# mobile-lipo-charger-v0001.net
KiCad netlist of a schematic drawn in EAGLE
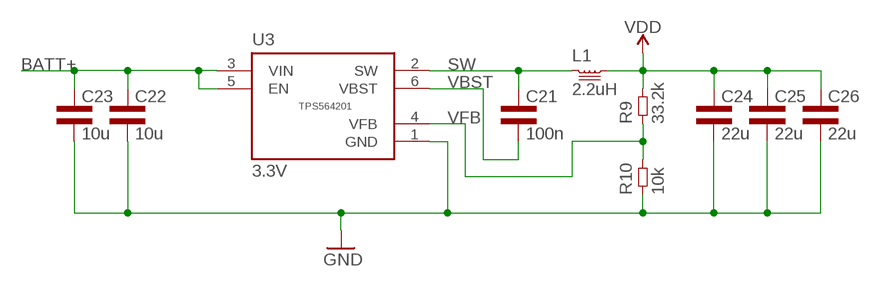
[diagram p0: schematic, sheet 1]
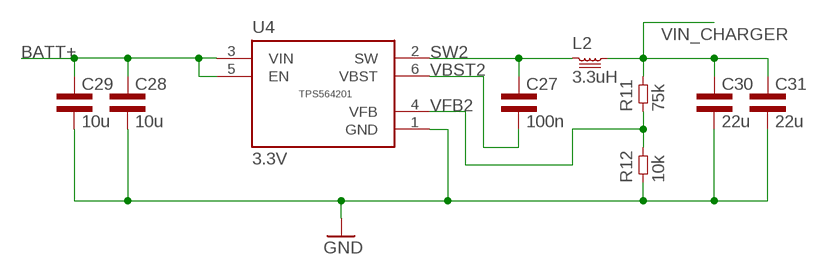
[diagram p1: schematic, sheet 2]
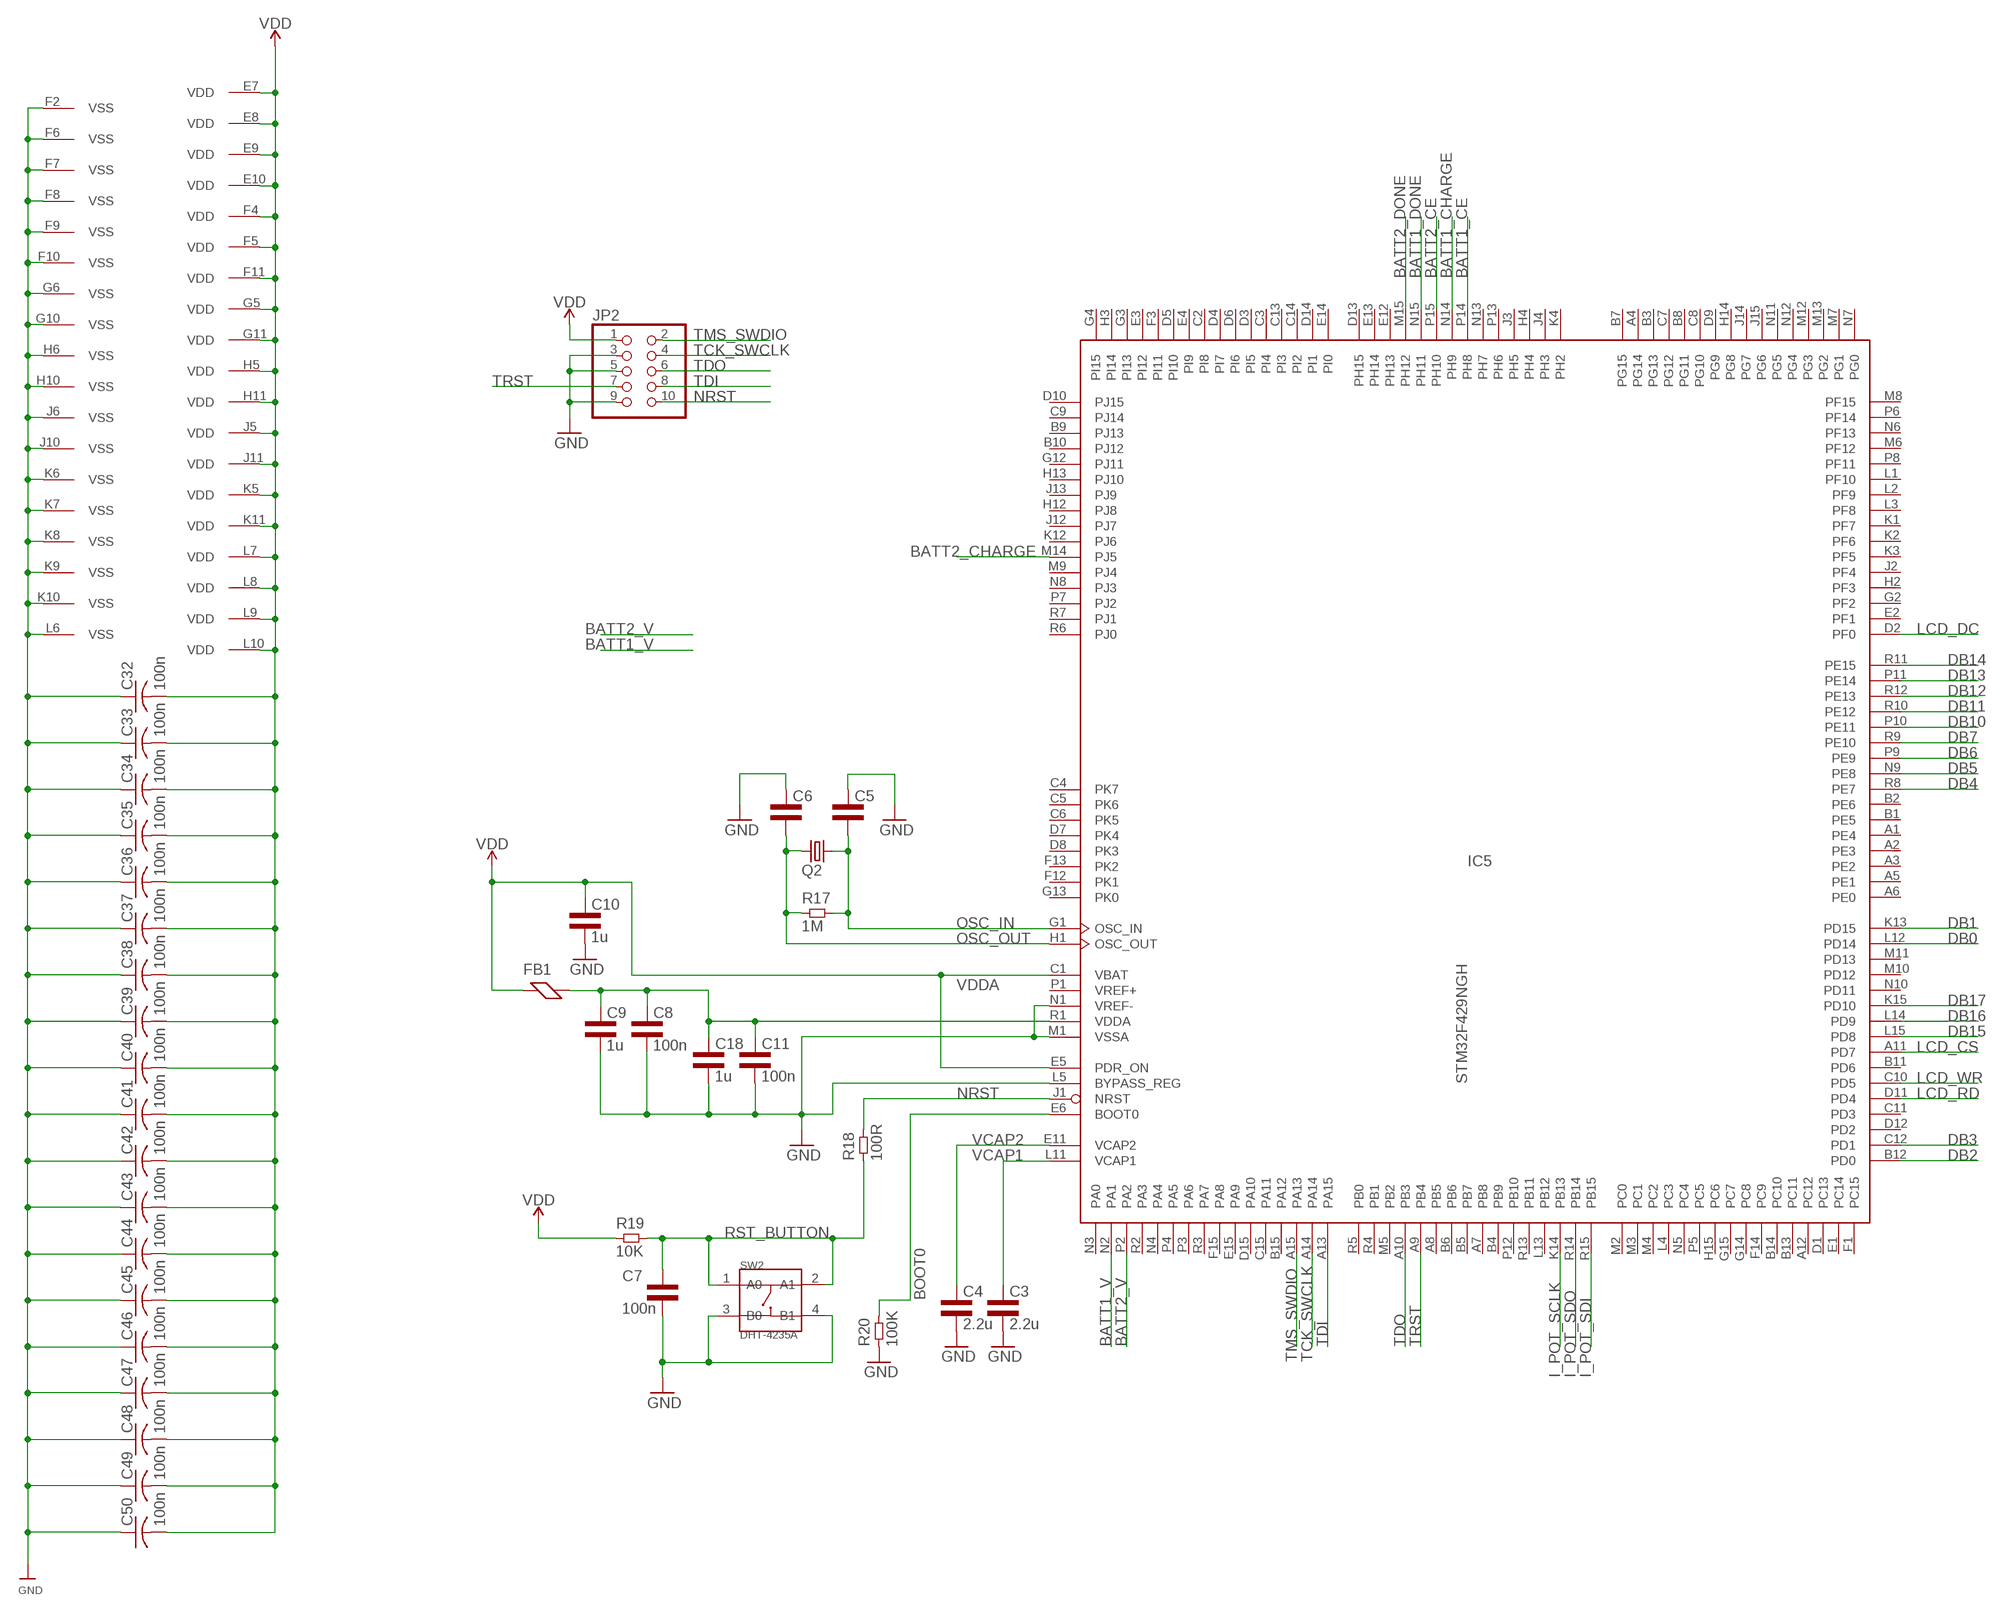
[diagram p2: schematic, sheet 3]
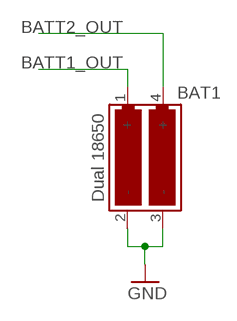
[diagram p3: schematic, sheet 4]
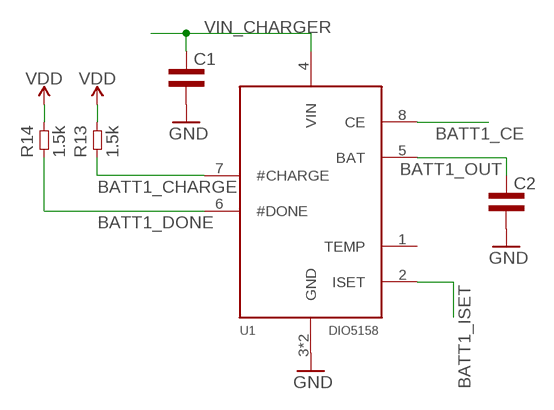
[diagram p4: schematic, sheet 5]
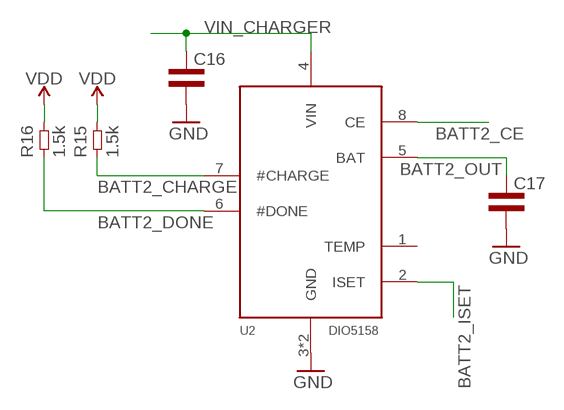
[diagram p5: schematic, sheet 6]
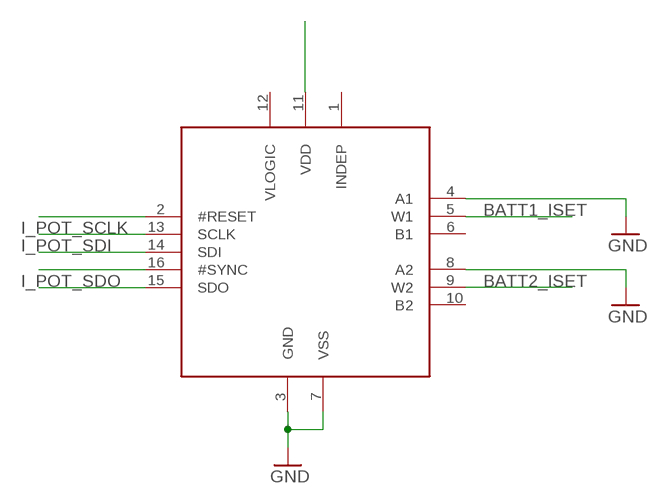
[diagram p6: schematic, sheet 7]
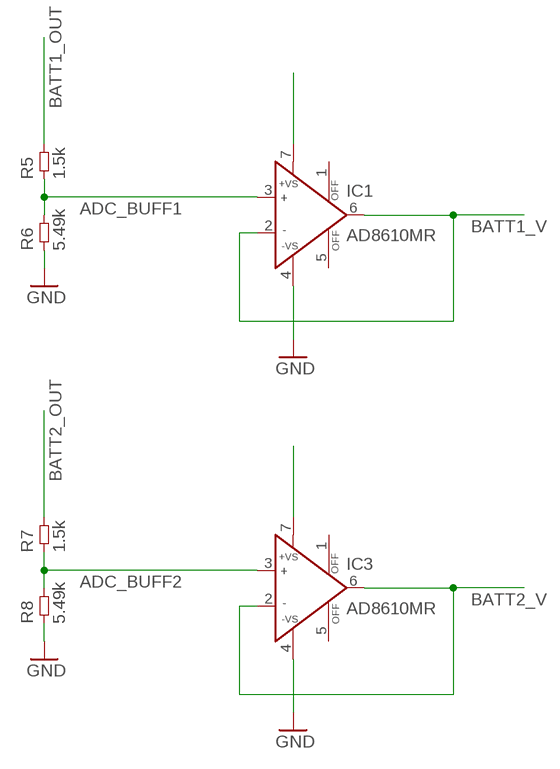
[diagram p7: schematic, sheet 8]
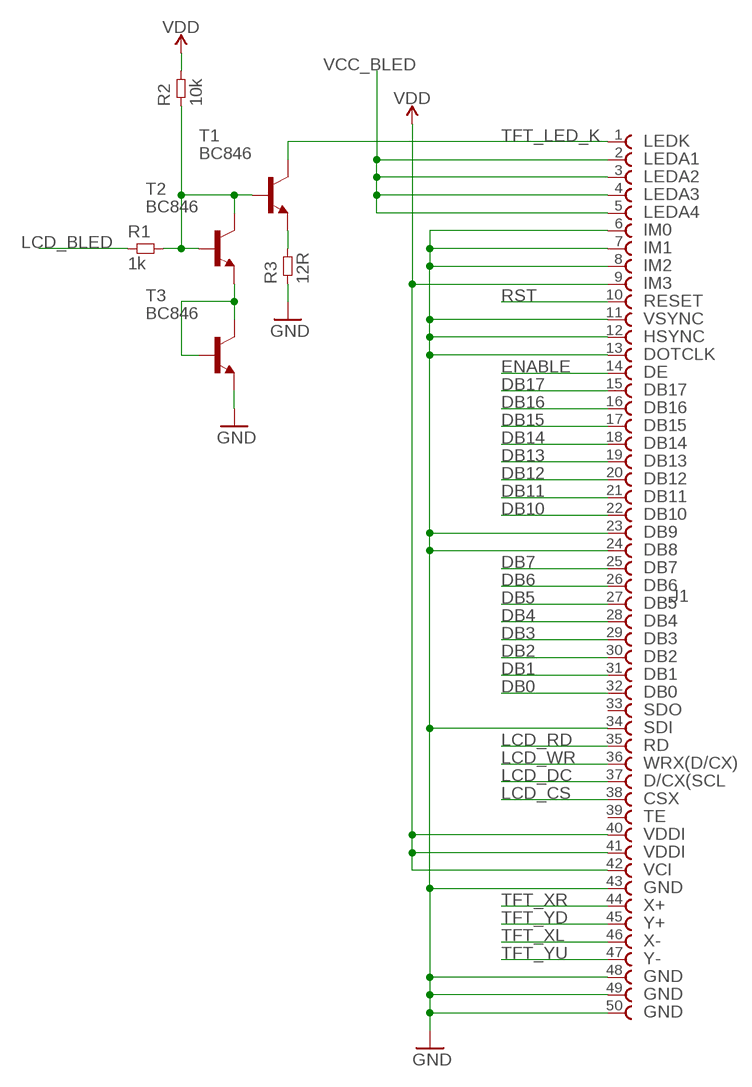
[diagram p8: schematic, sheet 9]

(export (version "E")
  (design (tool "Eeschema 10.0.6"))
  (components
    (comp (ref "C16")
      (value "CAP0805L3")
      (footprint "eagle-import:0805L3")
      (libsource (lib "eagle-import") (part "CAP0805L3"))
    )
    (comp (ref "C17")
      (value "CAP0805L3")
      (footprint "eagle-import:0805L3")
      (libsource (lib "eagle-import") (part "CAP0805L3"))
    )
    (comp (ref "R15")
      (value "1.5k")
      (footprint "eagle-import:0603L3")
      (libsource (lib "eagle-import") (part "RES0603L3"))
    )
    (comp (ref "R16")
      (value "1.5k")
      (footprint "eagle-import:0603L3")
      (libsource (lib "eagle-import") (part "RES0603L3"))
    )
    (comp (ref "U2")
      (value "DIO5158XS8")
      (footprint "eagle-import:EP-MSOP8")
      (libsource (lib "eagle-import") (part "DIO5158XS8"))
    )
    (comp (ref "C3")
      (value "2.2u")
      (footprint "eagle-import:0805L3")
      (fields (field (name "MANUFACTURER") "AVX"))
      (libsource (lib "eagle-import") (part "CAP0805L3"))
    )
    (comp (ref "C4")
      (value "2.2u")
      (footprint "eagle-import:0805L3")
      (fields (field (name "MANUFACTURER") "AVX"))
      (libsource (lib "eagle-import") (part "CAP0805L3"))
    )
    (comp (ref "C5")
      (value "CAP0603L3")
      (footprint "eagle-import:0603L3")
      (libsource (lib "eagle-import") (part "CAP0603L3"))
    )
    (comp (ref "C6")
      (value "CAP0603L3")
      (footprint "eagle-import:0603L3")
      (libsource (lib "eagle-import") (part "CAP0603L3"))
    )
    (comp (ref "C7")
      (value "100n")
      (footprint "eagle-import:0402L3")
      (libsource (lib "eagle-import") (part "CAP0402L3"))
    )
    (comp (ref "C8")
      (value "100n")
      (footprint "eagle-import:0402L3")
      (libsource (lib "eagle-import") (part "CAP0402L3"))
    )
    (comp (ref "C9")
      (value "1u")
      (footprint "eagle-import:0805L3")
      (libsource (lib "eagle-import") (part "CAP0805L3"))
    )
    (comp (ref "C10")
      (value "1u")
      (footprint "eagle-import:0603L3")
      (libsource (lib "eagle-import") (part "CAP0603L3"))
    )
    (comp (ref "C11")
      (value "100n")
      (footprint "eagle-import:0402L3")
      (libsource (lib "eagle-import") (part "CAP0402L3"))
    )
    (comp (ref "C18")
      (value "1u")
      (footprint "eagle-import:0805L3")
      (libsource (lib "eagle-import") (part "CAP0805L3"))
    )
    (comp (ref "C32")
      (value "100n")
      (footprint "eagle-import:C0201")
      (libsource (lib "eagle-import") (part "C-USC0201"))
    )
    (comp (ref "C33")
      (value "100n")
      (footprint "eagle-import:C0201")
      (libsource (lib "eagle-import") (part "C-USC0201"))
    )
    (comp (ref "C34")
      (value "100n")
      (footprint "eagle-import:C0201")
      (libsource (lib "eagle-import") (part "C-USC0201"))
    )
    (comp (ref "C35")
      (value "100n")
      (footprint "eagle-import:C0201")
      (libsource (lib "eagle-import") (part "C-USC0201"))
    )
    (comp (ref "C36")
      (value "100n")
      (footprint "eagle-import:C0201")
      (libsource (lib "eagle-import") (part "C-USC0201"))
    )
    (comp (ref "C37")
      (value "100n")
      (footprint "eagle-import:C0201")
      (libsource (lib "eagle-import") (part "C-USC0201"))
    )
    (comp (ref "C38")
      (value "100n")
      (footprint "eagle-import:C0201")
      (libsource (lib "eagle-import") (part "C-USC0201"))
    )
    (comp (ref "C39")
      (value "100n")
      (footprint "eagle-import:C0201")
      (libsource (lib "eagle-import") (part "C-USC0201"))
    )
    (comp (ref "C40")
      (value "100n")
      (footprint "eagle-import:C0201")
      (libsource (lib "eagle-import") (part "C-USC0201"))
    )
    (comp (ref "C41")
      (value "100n")
      (footprint "eagle-import:C0201")
      (libsource (lib "eagle-import") (part "C-USC0201"))
    )
    (comp (ref "C42")
      (value "100n")
      (footprint "eagle-import:C0201")
      (libsource (lib "eagle-import") (part "C-USC0201"))
    )
    (comp (ref "C43")
      (value "100n")
      (footprint "eagle-import:C0201")
      (libsource (lib "eagle-import") (part "C-USC0201"))
    )
    (comp (ref "C44")
      (value "100n")
      (footprint "eagle-import:C0201")
      (libsource (lib "eagle-import") (part "C-USC0201"))
    )
    (comp (ref "C45")
      (value "100n")
      (footprint "eagle-import:C0201")
      (libsource (lib "eagle-import") (part "C-USC0201"))
    )
    (comp (ref "C46")
      (value "100n")
      (footprint "eagle-import:C0201")
      (libsource (lib "eagle-import") (part "C-USC0201"))
    )
    (comp (ref "C47")
      (value "100n")
      (footprint "eagle-import:C0201")
      (libsource (lib "eagle-import") (part "C-USC0201"))
    )
    (comp (ref "C48")
      (value "100n")
      (footprint "eagle-import:C0201")
      (libsource (lib "eagle-import") (part "C-USC0201"))
    )
    (comp (ref "C49")
      (value "100n")
      (footprint "eagle-import:C0201")
      (libsource (lib "eagle-import") (part "C-USC0201"))
    )
    (comp (ref "C50")
      (value "100n")
      (footprint "eagle-import:C0201")
      (libsource (lib "eagle-import") (part "C-USC0201"))
    )
    (comp (ref "FB1")
      (value "FERRITE0603L3")
      (footprint "eagle-import:0603L3")
      (libsource (lib "eagle-import") (part "FERRITE0603L3"))
    )
    (comp (ref "IC5")
      (value "STM32F429NGH")
      (footprint "eagle-import:TFBGA216")
      (libsource (lib "eagle-import") (part "STM32F429NHG"))
    )
    (comp (ref "JP2")
      (value "PINHD-2X5")
      (footprint "eagle-import:2X05")
      (libsource (lib "eagle-import") (part "PINHD-2X5"))
    )
    (comp (ref "Q2")
      (value "CRYSTALHC49US")
      (footprint "eagle-import:PCM2707_V1_SPARKFUN_HC49US")
      (libsource (lib "eagle-import") (part "CRYSTALHC49US"))
    )
    (comp (ref "R17")
      (value "1M")
      (footprint "eagle-import:0603L3")
      (libsource (lib "eagle-import") (part "RES0603L3"))
    )
    (comp (ref "R18")
      (value "100R")
      (footprint "eagle-import:0603L3")
      (libsource (lib "eagle-import") (part "RES0603L3"))
    )
    (comp (ref "R19")
      (value "10K")
      (footprint "eagle-import:0603L3")
      (libsource (lib "eagle-import") (part "RES0603L3"))
    )
    (comp (ref "R20")
      (value "100K")
      (footprint "eagle-import:0603L3")
      (libsource (lib "eagle-import") (part "RES0603L3"))
    )
    (comp (ref "SW2")
      (value "DHT-4235A")
      (footprint "eagle-import:SW4-SMD-4.2X3.2X2.5MM")
      (libsource (lib "eagle-import") (part "SMD-BUTTON-TOP-DHT-4235A(4P-4.2X3.2MM)"))
    )
    (comp (ref "U$1")
      (value "AD5122BRUZ10")
      (footprint "eagle-import:TSSOP-RU-16")
      (fields (field (name "MANUFACTURER") "Analog Devices"))
      (libsource (lib "eagle-import") (part "AD5122BRUZ10"))
    )
    (comp (ref "C27")
      (value "100n")
      (footprint "eagle-import:0603L3")
      (libsource (lib "eagle-import") (part "CAP0603L3"))
    )
    (comp (ref "C28")
      (value "10u")
      (footprint "eagle-import:1206L3")
      (libsource (lib "eagle-import") (part "CAP1206L3"))
    )
    (comp (ref "C29")
      (value "10u")
      (footprint "eagle-import:1206L3")
      (libsource (lib "eagle-import") (part "CAP1206L3"))
    )
    (comp (ref "C30")
      (value "22u")
      (footprint "eagle-import:0603L3")
      (libsource (lib "eagle-import") (part "CAP0603L3"))
    )
    (comp (ref "C31")
      (value "22u")
      (footprint "eagle-import:0603L3")
      (libsource (lib "eagle-import") (part "CAP0603L3"))
    )
    (comp (ref "L2")
      (value "3.3uH")
      (footprint "eagle-import:6X6")
      (fields (field (name "MANUFACTURER") "TDK"))
      (libsource (lib "eagle-import") (part "INDUCTOR6X6"))
    )
    (comp (ref "R11")
      (value "75k")
      (footprint "eagle-import:0402L3")
      (libsource (lib "eagle-import") (part "RES0402L3"))
    )
    (comp (ref "R12")
      (value "10k")
      (footprint "eagle-import:0402L3")
      (libsource (lib "eagle-import") (part "RES0402L3"))
    )
    (comp (ref "U4")
      (value "3.3V")
      (footprint "eagle-import:SOT-1.1")
      (libsource (lib "eagle-import") (part "TPS564201"))
    )
    (comp (ref "BAT1")
      (value "KEYSTONE1048")
      (footprint "eagle-import:KEYSTONE1048")
      (libsource (lib "eagle-import") (part "KEYSTONE1048"))
    )
    (comp (ref "C1")
      (value "CAP0805L3")
      (footprint "eagle-import:0805L3")
      (libsource (lib "eagle-import") (part "CAP0805L3"))
    )
    (comp (ref "C2")
      (value "CAP0805L3")
      (footprint "eagle-import:0805L3")
      (libsource (lib "eagle-import") (part "CAP0805L3"))
    )
    (comp (ref "R13")
      (value "1.5k")
      (footprint "eagle-import:0603L3")
      (libsource (lib "eagle-import") (part "RES0603L3"))
    )
    (comp (ref "R14")
      (value "1.5k")
      (footprint "eagle-import:0603L3")
      (libsource (lib "eagle-import") (part "RES0603L3"))
    )
    (comp (ref "U1")
      (value "DIO5158XS8")
      (footprint "eagle-import:EP-MSOP8")
      (libsource (lib "eagle-import") (part "DIO5158XS8"))
    )
    (comp (ref "J1")
      (value "68715014022")
      (footprint "eagle-import:68715014022")
      (libsource (lib "eagle-import") (part "68715014022"))
    )
    (comp (ref "R1")
      (value "1k")
      (footprint "eagle-import:0603L3")
      (libsource (lib "eagle-import") (part "RES0603L3"))
    )
    (comp (ref "R2")
      (value "10k")
      (footprint "eagle-import:0603L3")
      (libsource (lib "eagle-import") (part "RES0603L3"))
    )
    (comp (ref "R3")
      (value "12R")
      (footprint "eagle-import:0603L3")
      (libsource (lib "eagle-import") (part "RES0603L3"))
    )
    (comp (ref "T1")
      (value "BC846")
      (footprint "eagle-import:SOT23")
      (libsource (lib "eagle-import") (part "BC846"))
    )
    (comp (ref "T2")
      (value "BC846")
      (footprint "eagle-import:SOT23")
      (libsource (lib "eagle-import") (part "BC846"))
    )
    (comp (ref "T3")
      (value "BC846")
      (footprint "eagle-import:SOT23")
      (libsource (lib "eagle-import") (part "BC846"))
    )
    (comp (ref "IC1")
      (value "AD8610MR")
      (footprint "eagle-import:MSOP08")
      (fields (field (name "MF") "ALTERA CORPORATION") (field (name "MPN") "AD8610ARMZ-REEL"))
      (libsource (lib "eagle-import") (part "AD8610MR"))
    )
    (comp (ref "IC3")
      (value "AD8610MR")
      (footprint "eagle-import:MSOP08")
      (fields (field (name "MF") "ALTERA CORPORATION") (field (name "MPN") "AD8610ARMZ-REEL"))
      (libsource (lib "eagle-import") (part "AD8610MR"))
    )
    (comp (ref "R5")
      (value "1.5k")
      (footprint "eagle-import:0603L3")
      (libsource (lib "eagle-import") (part "RES0603L3"))
    )
    (comp (ref "R6")
      (value "5.49k")
      (footprint "eagle-import:0603L3")
      (libsource (lib "eagle-import") (part "RES0603L3"))
    )
    (comp (ref "R7")
      (value "1.5k")
      (footprint "eagle-import:0603L3")
      (libsource (lib "eagle-import") (part "RES0603L3"))
    )
    (comp (ref "R8")
      (value "5.49k")
      (footprint "eagle-import:0603L3")
      (libsource (lib "eagle-import") (part "RES0603L3"))
    )
    (comp (ref "C21")
      (value "100n")
      (footprint "eagle-import:0603L3")
      (libsource (lib "eagle-import") (part "CAP0603L3"))
    )
    (comp (ref "C22")
      (value "10u")
      (footprint "eagle-import:1206L3")
      (libsource (lib "eagle-import") (part "CAP1206L3"))
    )
    (comp (ref "C23")
      (value "10u")
      (footprint "eagle-import:1206L3")
      (libsource (lib "eagle-import") (part "CAP1206L3"))
    )
    (comp (ref "C24")
      (value "22u")
      (footprint "eagle-import:0603L3")
      (libsource (lib "eagle-import") (part "CAP0603L3"))
    )
    (comp (ref "C25")
      (value "22u")
      (footprint "eagle-import:0603L3")
      (libsource (lib "eagle-import") (part "CAP0603L3"))
    )
    (comp (ref "C26")
      (value "22u")
      (footprint "eagle-import:0603L3")
      (libsource (lib "eagle-import") (part "CAP0603L3"))
    )
    (comp (ref "L1")
      (value "2.2uH")
      (footprint "eagle-import:6X6")
      (fields (field (name "MANUFACTURER") "TDK"))
      (libsource (lib "eagle-import") (part "INDUCTOR6X6"))
    )
    (comp (ref "R9")
      (value "33.2k")
      (footprint "eagle-import:0402L3")
      (libsource (lib "eagle-import") (part "RES0402L3"))
    )
    (comp (ref "R10")
      (value "10k")
      (footprint "eagle-import:0402L3")
      (libsource (lib "eagle-import") (part "RES0402L3"))
    )
    (comp (ref "U3")
      (value "3.3V")
      (footprint "eagle-import:SOT-1.1")
      (libsource (lib "eagle-import") (part "TPS564201"))
    )
  )
  (nets
    (net (code "1") (name "ADC_BUFF1") (class "Default")
      (node (ref "IC1") (pin "3") (pinfunction "IN+_3") (pintype "input"))
      (node (ref "R5") (pin "P$1") (pinfunction "1_P$1") (pintype "bidirectional"))
      (node (ref "R6") (pin "P$2") (pinfunction "2_P$2") (pintype "bidirectional"))
    )
    (net (code "2") (name "ADC_BUFF2") (class "Default")
      (node (ref "IC3") (pin "3") (pinfunction "IN+_3") (pintype "input"))
      (node (ref "R7") (pin "P$1") (pinfunction "1_P$1") (pintype "bidirectional"))
      (node (ref "R8") (pin "P$2") (pinfunction "2_P$2") (pintype "bidirectional"))
    )
    (net (code "3") (name "BATT+") (class "Default")
      (node (ref "C22") (pin "1") (pinfunction "1_1") (pintype "bidirectional"))
      (node (ref "C23") (pin "1") (pinfunction "1_1") (pintype "bidirectional"))
      (node (ref "C28") (pin "1") (pinfunction "1_1") (pintype "bidirectional"))
      (node (ref "C29") (pin "1") (pinfunction "1_1") (pintype "bidirectional"))
      (node (ref "U3") (pin "3") (pinfunction "VIN_3") (pintype "bidirectional"))
      (node (ref "U3") (pin "5") (pinfunction "EN_5") (pintype "bidirectional"))
      (node (ref "U4") (pin "3") (pinfunction "VIN_3") (pintype "bidirectional"))
      (node (ref "U4") (pin "5") (pinfunction "EN_5") (pintype "bidirectional"))
    )
    (net (code "4") (name "BATT1_CE") (class "Default")
      (node (ref "IC5") (pin "P14") (pinfunction "PH8_P14") (pintype "bidirectional"))
      (node (ref "U1") (pin "8") (pinfunction "CE_8") (pintype "bidirectional"))
    )
    (net (code "5") (name "BATT1_CHARGE") (class "Default")
      (node (ref "IC5") (pin "N14") (pinfunction "PH9_N14") (pintype "bidirectional"))
      (node (ref "R13") (pin "P$1") (pinfunction "1_P$1") (pintype "bidirectional"))
      (node (ref "U1") (pin "7") (pinfunction "#CHARGE_7") (pintype "bidirectional"))
    )
    (net (code "6") (name "BATT1_DONE") (class "Default")
      (node (ref "IC5") (pin "N15") (pinfunction "PH11_N15") (pintype "bidirectional"))
      (node (ref "R14") (pin "P$1") (pinfunction "1_P$1") (pintype "bidirectional"))
      (node (ref "U1") (pin "6") (pinfunction "#DONE_6") (pintype "bidirectional"))
    )
    (net (code "7") (name "BATT1_ISET") (class "Default")
      (node (ref "U$1") (pin "5") (pinfunction "W1_5") (pintype "bidirectional"))
      (node (ref "U1") (pin "2") (pinfunction "ISET_2") (pintype "bidirectional"))
    )
    (net (code "8") (name "BATT1_OUT") (class "Default")
      (node (ref "BAT1") (pin "1") (pinfunction "+_1") (pintype "bidirectional"))
      (node (ref "C2") (pin "1") (pinfunction "1_1") (pintype "bidirectional"))
      (node (ref "R5") (pin "P$2") (pinfunction "2_P$2") (pintype "bidirectional"))
      (node (ref "U1") (pin "5") (pinfunction "BAT_5") (pintype "bidirectional"))
    )
    (net (code "9") (name "BATT1_V") (class "Default")
      (node (ref "IC1") (pin "2") (pinfunction "IN-_2") (pintype "input"))
      (node (ref "IC1") (pin "6") (pinfunction "OUT_6") (pintype "output"))
      (node (ref "IC5") (pin "N2") (pinfunction "PA1_N2") (pintype "bidirectional"))
    )
    (net (code "10") (name "BATT2_CE") (class "Default")
      (node (ref "IC5") (pin "P15") (pinfunction "PH10_P15") (pintype "bidirectional"))
      (node (ref "U2") (pin "8") (pinfunction "CE_8") (pintype "bidirectional"))
    )
    (net (code "11") (name "BATT2_CHARGE") (class "Default")
      (node (ref "IC5") (pin "M14") (pinfunction "PJ5_M14") (pintype "bidirectional"))
      (node (ref "R15") (pin "P$1") (pinfunction "1_P$1") (pintype "bidirectional"))
      (node (ref "U2") (pin "7") (pinfunction "#CHARGE_7") (pintype "bidirectional"))
    )
    (net (code "12") (name "BATT2_DONE") (class "Default")
      (node (ref "IC5") (pin "M15") (pinfunction "PH12_M15") (pintype "bidirectional"))
      (node (ref "R16") (pin "P$1") (pinfunction "1_P$1") (pintype "bidirectional"))
      (node (ref "U2") (pin "6") (pinfunction "#DONE_6") (pintype "bidirectional"))
    )
    (net (code "13") (name "BATT2_ISET") (class "Default")
      (node (ref "U$1") (pin "9") (pinfunction "W2_9") (pintype "bidirectional"))
      (node (ref "U2") (pin "2") (pinfunction "ISET_2") (pintype "bidirectional"))
    )
    (net (code "14") (name "BATT2_OUT") (class "Default")
      (node (ref "BAT1") (pin "4") (pinfunction "+_4") (pintype "bidirectional"))
      (node (ref "C17") (pin "1") (pinfunction "1_1") (pintype "bidirectional"))
      (node (ref "R7") (pin "P$2") (pinfunction "2_P$2") (pintype "bidirectional"))
      (node (ref "U2") (pin "5") (pinfunction "BAT_5") (pintype "bidirectional"))
    )
    (net (code "15") (name "BATT2_V") (class "Default")
      (node (ref "IC3") (pin "2") (pinfunction "IN-_2") (pintype "input"))
      (node (ref "IC3") (pin "6") (pinfunction "OUT_6") (pintype "output"))
      (node (ref "IC5") (pin "P2") (pinfunction "PA2_P2") (pintype "bidirectional"))
    )
    (net (code "16") (name "BOOT0") (class "Default")
      (node (ref "IC5") (pin "E6") (pinfunction "BOOT0_E6") (pintype "input"))
      (node (ref "R20") (pin "P$2") (pinfunction "2_P$2") (pintype "bidirectional"))
    )
    (net (code "17") (name "DB0") (class "Default")
      (node (ref "IC5") (pin "L12") (pinfunction "PD14_L12") (pintype "bidirectional"))
      (node (ref "J1") (pin "32") (pinfunction "32_32") (pintype "passive"))
    )
    (net (code "18") (name "DB1") (class "Default")
      (node (ref "IC5") (pin "K13") (pinfunction "PD15_K13") (pintype "bidirectional"))
      (node (ref "J1") (pin "31") (pinfunction "31_31") (pintype "passive"))
    )
    (net (code "19") (name "DB2") (class "Default")
      (node (ref "IC5") (pin "B12") (pinfunction "PD0_B12") (pintype "bidirectional"))
      (node (ref "J1") (pin "30") (pinfunction "30_30") (pintype "passive"))
    )
    (net (code "20") (name "DB3") (class "Default")
      (node (ref "IC5") (pin "C12") (pinfunction "PD1_C12") (pintype "bidirectional"))
      (node (ref "J1") (pin "29") (pinfunction "29_29") (pintype "passive"))
    )
    (net (code "21") (name "DB4") (class "Default")
      (node (ref "IC5") (pin "R8") (pinfunction "PE7_R8") (pintype "bidirectional"))
      (node (ref "J1") (pin "28") (pinfunction "28_28") (pintype "passive"))
    )
    (net (code "22") (name "DB5") (class "Default")
      (node (ref "IC5") (pin "N9") (pinfunction "PE8_N9") (pintype "bidirectional"))
      (node (ref "J1") (pin "27") (pinfunction "27_27") (pintype "passive"))
    )
    (net (code "23") (name "DB6") (class "Default")
      (node (ref "IC5") (pin "P9") (pinfunction "PE9_P9") (pintype "bidirectional"))
      (node (ref "J1") (pin "26") (pinfunction "26_26") (pintype "passive"))
    )
    (net (code "24") (name "DB7") (class "Default")
      (node (ref "IC5") (pin "R9") (pinfunction "PE10_R9") (pintype "bidirectional"))
      (node (ref "J1") (pin "25") (pinfunction "25_25") (pintype "passive"))
    )
    (net (code "25") (name "DB10") (class "Default")
      (node (ref "IC5") (pin "P10") (pinfunction "PE11_P10") (pintype "bidirectional"))
      (node (ref "J1") (pin "22") (pinfunction "22_22") (pintype "passive"))
    )
    (net (code "26") (name "DB11") (class "Default")
      (node (ref "IC5") (pin "R10") (pinfunction "PE12_R10") (pintype "bidirectional"))
      (node (ref "J1") (pin "21") (pinfunction "21_21") (pintype "passive"))
    )
    (net (code "27") (name "DB12") (class "Default")
      (node (ref "IC5") (pin "R12") (pinfunction "PE13_R12") (pintype "bidirectional"))
      (node (ref "J1") (pin "20") (pinfunction "20_20") (pintype "passive"))
    )
    (net (code "28") (name "DB13") (class "Default")
      (node (ref "IC5") (pin "P11") (pinfunction "PE14_P11") (pintype "bidirectional"))
      (node (ref "J1") (pin "19") (pinfunction "19_19") (pintype "passive"))
    )
    (net (code "29") (name "DB14") (class "Default")
      (node (ref "IC5") (pin "R11") (pinfunction "PE15_R11") (pintype "bidirectional"))
      (node (ref "J1") (pin "18") (pinfunction "18_18") (pintype "passive"))
    )
    (net (code "30") (name "DB15") (class "Default")
      (node (ref "IC5") (pin "L15") (pinfunction "PD8_L15") (pintype "bidirectional"))
      (node (ref "J1") (pin "17") (pinfunction "17_17") (pintype "passive"))
    )
    (net (code "31") (name "DB16") (class "Default")
      (node (ref "IC5") (pin "L14") (pinfunction "PD9_L14") (pintype "bidirectional"))
      (node (ref "J1") (pin "16") (pinfunction "16_16") (pintype "passive"))
    )
    (net (code "32") (name "DB17") (class "Default")
      (node (ref "IC5") (pin "K15") (pinfunction "PD10_K15") (pintype "bidirectional"))
      (node (ref "J1") (pin "15") (pinfunction "15_15") (pintype "passive"))
    )
    (net (code "33") (name "ENABLE") (class "Default")
      (node (ref "J1") (pin "14") (pinfunction "14_14") (pintype "passive"))
    )
    (net (code "34") (name "GND") (class "Default")
      (node (ref "BAT1") (pin "2") (pinfunction "-_2") (pintype "bidirectional"))
      (node (ref "BAT1") (pin "3") (pinfunction "-_3") (pintype "bidirectional"))
      (node (ref "C1") (pin "2") (pinfunction "2_2") (pintype "bidirectional"))
      (node (ref "C10") (pin "P$2") (pinfunction "2_P$2") (pintype "bidirectional"))
      (node (ref "C11") (pin "P$2") (pinfunction "2_P$2") (pintype "bidirectional"))
      (node (ref "C16") (pin "2") (pinfunction "2_2") (pintype "bidirectional"))
      (node (ref "C17") (pin "2") (pinfunction "2_2") (pintype "bidirectional"))
      (node (ref "C18") (pin "2") (pinfunction "2_2") (pintype "bidirectional"))
      (node (ref "C2") (pin "2") (pinfunction "2_2") (pintype "bidirectional"))
      (node (ref "C22") (pin "2") (pinfunction "2_2") (pintype "bidirectional"))
      (node (ref "C23") (pin "2") (pinfunction "2_2") (pintype "bidirectional"))
      (node (ref "C24") (pin "P$2") (pinfunction "2_P$2") (pintype "bidirectional"))
      (node (ref "C25") (pin "P$2") (pinfunction "2_P$2") (pintype "bidirectional"))
      (node (ref "C26") (pin "P$2") (pinfunction "2_P$2") (pintype "bidirectional"))
      (node (ref "C28") (pin "2") (pinfunction "2_2") (pintype "bidirectional"))
      (node (ref "C29") (pin "2") (pinfunction "2_2") (pintype "bidirectional"))
      (node (ref "C3") (pin "2") (pinfunction "2_2") (pintype "bidirectional"))
      (node (ref "C30") (pin "P$2") (pinfunction "2_P$2") (pintype "bidirectional"))
      (node (ref "C31") (pin "P$2") (pinfunction "2_P$2") (pintype "bidirectional"))
      (node (ref "C32") (pin "1") (pinfunction "1_1") (pintype "passive"))
      (node (ref "C33") (pin "1") (pinfunction "1_1") (pintype "passive"))
      (node (ref "C34") (pin "1") (pinfunction "1_1") (pintype "passive"))
      (node (ref "C35") (pin "1") (pinfunction "1_1") (pintype "passive"))
      (node (ref "C36") (pin "1") (pinfunction "1_1") (pintype "passive"))
      (node (ref "C37") (pin "1") (pinfunction "1_1") (pintype "passive"))
      (node (ref "C38") (pin "1") (pinfunction "1_1") (pintype "passive"))
      (node (ref "C39") (pin "1") (pinfunction "1_1") (pintype "passive"))
      (node (ref "C4") (pin "2") (pinfunction "2_2") (pintype "bidirectional"))
      (node (ref "C40") (pin "1") (pinfunction "1_1") (pintype "passive"))
      (node (ref "C41") (pin "1") (pinfunction "1_1") (pintype "passive"))
      (node (ref "C42") (pin "1") (pinfunction "1_1") (pintype "passive"))
      (node (ref "C43") (pin "1") (pinfunction "1_1") (pintype "passive"))
      (node (ref "C44") (pin "1") (pinfunction "1_1") (pintype "passive"))
      (node (ref "C45") (pin "1") (pinfunction "1_1") (pintype "passive"))
      (node (ref "C46") (pin "1") (pinfunction "1_1") (pintype "passive"))
      (node (ref "C47") (pin "1") (pinfunction "1_1") (pintype "passive"))
      (node (ref "C48") (pin "1") (pinfunction "1_1") (pintype "passive"))
      (node (ref "C49") (pin "1") (pinfunction "1_1") (pintype "passive"))
      (node (ref "C5") (pin "P$1") (pinfunction "1_P$1") (pintype "bidirectional"))
      (node (ref "C50") (pin "1") (pinfunction "1_1") (pintype "passive"))
      (node (ref "C6") (pin "P$1") (pinfunction "1_P$1") (pintype "bidirectional"))
      (node (ref "C7") (pin "P$2") (pinfunction "2_P$2") (pintype "bidirectional"))
      (node (ref "C8") (pin "P$2") (pinfunction "2_P$2") (pintype "bidirectional"))
      (node (ref "C9") (pin "2") (pinfunction "2_2") (pintype "bidirectional"))
      (node (ref "IC1") (pin "4") (pinfunction "-VS_4") (pintype "input"))
      (node (ref "IC3") (pin "4") (pinfunction "-VS_4") (pintype "input"))
      (node (ref "IC5") (pin "F10") (pinfunction "VSS_F10") (pintype "power_in"))
      (node (ref "IC5") (pin "F2") (pinfunction "VSS_F2") (pintype "power_in"))
      (node (ref "IC5") (pin "F6") (pinfunction "VSS_F6") (pintype "power_in"))
      (node (ref "IC5") (pin "F7") (pinfunction "VSS_F7") (pintype "power_in"))
      (node (ref "IC5") (pin "F8") (pinfunction "VSS_F8") (pintype "power_in"))
      (node (ref "IC5") (pin "F9") (pinfunction "VSS_F9") (pintype "power_in"))
      (node (ref "IC5") (pin "G10") (pinfunction "VSS_G10") (pintype "power_in"))
      (node (ref "IC5") (pin "G6") (pinfunction "VSS_G6") (pintype "power_in"))
      (node (ref "IC5") (pin "H10") (pinfunction "VSS_H10") (pintype "power_in"))
      (node (ref "IC5") (pin "H6") (pinfunction "VSS_H6") (pintype "power_in"))
      (node (ref "IC5") (pin "J10") (pinfunction "VSS_J10") (pintype "power_in"))
      (node (ref "IC5") (pin "J6") (pinfunction "VSS_J6") (pintype "power_in"))
      (node (ref "IC5") (pin "K10") (pinfunction "VSS_K10") (pintype "power_in"))
      (node (ref "IC5") (pin "K6") (pinfunction "VSS_K6") (pintype "power_in"))
      (node (ref "IC5") (pin "K7") (pinfunction "VSS_K7") (pintype "power_in"))
      (node (ref "IC5") (pin "K8") (pinfunction "VSS_K8") (pintype "power_in"))
      (node (ref "IC5") (pin "K9") (pinfunction "VSS_K9") (pintype "power_in"))
      (node (ref "IC5") (pin "L5") (pinfunction "BYPASS_REG_L5") (pintype "input"))
      (node (ref "IC5") (pin "L6") (pinfunction "VSS_L6") (pintype "power_in"))
      (node (ref "IC5") (pin "M1") (pinfunction "VSSA_M1") (pintype "power_in"))
      (node (ref "IC5") (pin "N1") (pinfunction "VREF-_N1") (pintype "power_in"))
      (node (ref "J1") (pin "11") (pinfunction "11_11") (pintype "passive"))
      (node (ref "J1") (pin "12") (pinfunction "12_12") (pintype "passive"))
      (node (ref "J1") (pin "13") (pinfunction "13_13") (pintype "passive"))
      (node (ref "J1") (pin "23") (pinfunction "23_23") (pintype "passive"))
      (node (ref "J1") (pin "24") (pinfunction "24_24") (pintype "passive"))
      (node (ref "J1") (pin "34") (pinfunction "34_34") (pintype "passive"))
      (node (ref "J1") (pin "43") (pinfunction "43_43") (pintype "passive"))
      (node (ref "J1") (pin "48") (pinfunction "48_48") (pintype "passive"))
      (node (ref "J1") (pin "49") (pinfunction "49_49") (pintype "passive"))
      (node (ref "J1") (pin "50") (pinfunction "50_50") (pintype "passive"))
      (node (ref "J1") (pin "6") (pinfunction "6_6") (pintype "passive"))
      (node (ref "J1") (pin "7") (pinfunction "7_7") (pintype "passive"))
      (node (ref "J1") (pin "8") (pinfunction "8_8") (pintype "passive"))
      (node (ref "JP2") (pin "3") (pinfunction "3_3") (pintype "passive"))
      (node (ref "JP2") (pin "5") (pinfunction "5_5") (pintype "passive"))
      (node (ref "JP2") (pin "9") (pinfunction "9_9") (pintype "passive"))
      (node (ref "R10") (pin "P$1") (pinfunction "1_P$1") (pintype "bidirectional"))
      (node (ref "R12") (pin "P$1") (pinfunction "1_P$1") (pintype "bidirectional"))
      (node (ref "R20") (pin "P$1") (pinfunction "1_P$1") (pintype "bidirectional"))
      (node (ref "R3") (pin "P$1") (pinfunction "1_P$1") (pintype "bidirectional"))
      (node (ref "R6") (pin "P$1") (pinfunction "1_P$1") (pintype "bidirectional"))
      (node (ref "R8") (pin "P$1") (pinfunction "1_P$1") (pintype "bidirectional"))
      (node (ref "SW2") (pin "3") (pinfunction "B0_3") (pintype "bidirectional"))
      (node (ref "SW2") (pin "4") (pinfunction "B1_4") (pintype "bidirectional"))
      (node (ref "T3") (pin "2") (pinfunction "E_2") (pintype "passive"))
      (node (ref "U$1") (pin "3") (pinfunction "GND_3") (pintype "bidirectional"))
      (node (ref "U$1") (pin "4") (pinfunction "A1_4") (pintype "bidirectional"))
      (node (ref "U$1") (pin "7") (pinfunction "VSS_7") (pintype "bidirectional"))
      (node (ref "U$1") (pin "8") (pinfunction "A2_8") (pintype "bidirectional"))
      (node (ref "U1") (pin "3") (pinfunction "GND_3") (pintype "bidirectional"))
      (node (ref "U1") (pin "TP") (pinfunction "GND_TP") (pintype "bidirectional"))
      (node (ref "U2") (pin "3") (pinfunction "GND_3") (pintype "bidirectional"))
      (node (ref "U2") (pin "TP") (pinfunction "GND_TP") (pintype "bidirectional"))
      (node (ref "U3") (pin "1") (pinfunction "GND_1") (pintype "bidirectional"))
      (node (ref "U4") (pin "1") (pinfunction "GND_1") (pintype "bidirectional"))
    )
    (net (code "35") (name "I_POT_SCLK") (class "Default")
      (node (ref "IC5") (pin "K14") (pinfunction "PB13_K14") (pintype "bidirectional"))
      (node (ref "U$1") (pin "13") (pinfunction "SCLK_13") (pintype "bidirectional"))
    )
    (net (code "36") (name "I_POT_SDI") (class "Default")
      (node (ref "IC5") (pin "R15") (pinfunction "PB15_R15") (pintype "bidirectional"))
      (node (ref "U$1") (pin "14") (pinfunction "SDI_14") (pintype "bidirectional"))
    )
    (net (code "37") (name "I_POT_SDO") (class "Default")
      (node (ref "IC5") (pin "R14") (pinfunction "PB14_R14") (pintype "bidirectional"))
      (node (ref "U$1") (pin "15") (pinfunction "SDO_15") (pintype "bidirectional"))
    )
    (net (code "38") (name "LCD_BLED") (class "Default")
      (node (ref "R1") (pin "P$1") (pinfunction "1_P$1") (pintype "bidirectional"))
    )
    (net (code "39") (name "LCD_CS") (class "Default")
      (node (ref "IC5") (pin "A11") (pinfunction "PD7_A11") (pintype "bidirectional"))
      (node (ref "J1") (pin "38") (pinfunction "38_38") (pintype "passive"))
    )
    (net (code "40") (name "LCD_DC") (class "Default")
      (node (ref "IC5") (pin "D2") (pinfunction "PF0_D2") (pintype "bidirectional"))
      (node (ref "J1") (pin "37") (pinfunction "37_37") (pintype "passive"))
    )
    (net (code "41") (name "LCD_RD") (class "Default")
      (node (ref "IC5") (pin "D11") (pinfunction "PD4_D11") (pintype "bidirectional"))
      (node (ref "J1") (pin "35") (pinfunction "35_35") (pintype "passive"))
    )
    (net (code "42") (name "LCD_WR") (class "Default")
      (node (ref "IC5") (pin "C10") (pinfunction "PD5_C10") (pintype "bidirectional"))
      (node (ref "J1") (pin "36") (pinfunction "36_36") (pintype "passive"))
    )
    (net (code "43") (name "NRST") (class "Default")
      (node (ref "IC5") (pin "J1") (pinfunction "NRST_J1") (pintype "bidirectional"))
      (node (ref "JP2") (pin "10") (pinfunction "10_10") (pintype "passive"))
      (node (ref "R18") (pin "P$2") (pinfunction "2_P$2") (pintype "bidirectional"))
    )
    (net (code "44") (name "Net-(R1-2)") (class "Default")
      (node (ref "R1") (pin "P$2") (pinfunction "2_P$2") (pintype "bidirectional"))
      (node (ref "R2") (pin "P$1") (pinfunction "1_P$1") (pintype "bidirectional"))
      (node (ref "T1") (pin "1") (pinfunction "B_1") (pintype "passive"))
      (node (ref "T2") (pin "1") (pinfunction "B_1") (pintype "passive"))
      (node (ref "T2") (pin "3") (pinfunction "C_3") (pintype "passive"))
    )
    (net (code "45") (name "Net-(R3-2)") (class "Default")
      (node (ref "R3") (pin "P$2") (pinfunction "2_P$2") (pintype "bidirectional"))
      (node (ref "T1") (pin "2") (pinfunction "E_2") (pintype "passive"))
    )
    (net (code "46") (name "Net-(T2-E)") (class "Default")
      (node (ref "T2") (pin "2") (pinfunction "E_2") (pintype "passive"))
      (node (ref "T3") (pin "1") (pinfunction "B_1") (pintype "passive"))
      (node (ref "T3") (pin "3") (pinfunction "C_3") (pintype "passive"))
    )
    (net (code "47") (name "OSC_IN") (class "Default")
      (node (ref "C5") (pin "P$2") (pinfunction "2_P$2") (pintype "bidirectional"))
      (node (ref "IC5") (pin "G1") (pinfunction "OSC_IN_G1") (pintype "bidirectional"))
      (node (ref "Q2") (pin "2") (pinfunction "2_2") (pintype "passive"))
      (node (ref "R17") (pin "P$2") (pinfunction "2_P$2") (pintype "bidirectional"))
    )
    (net (code "48") (name "OSC_OUT") (class "Default")
      (node (ref "C6") (pin "P$2") (pinfunction "2_P$2") (pintype "bidirectional"))
      (node (ref "IC5") (pin "H1") (pinfunction "OSC_OUT_H1") (pintype "bidirectional"))
      (node (ref "Q2") (pin "1") (pinfunction "1_1") (pintype "passive"))
      (node (ref "R17") (pin "P$1") (pinfunction "1_P$1") (pintype "bidirectional"))
    )
    (net (code "49") (name "RST") (class "Default")
      (node (ref "J1") (pin "10") (pinfunction "10_10") (pintype "passive"))
    )
    (net (code "50") (name "RST_BUTTON") (class "Default")
      (node (ref "C7") (pin "P$1") (pinfunction "1_P$1") (pintype "bidirectional"))
      (node (ref "R18") (pin "P$1") (pinfunction "1_P$1") (pintype "bidirectional"))
      (node (ref "R19") (pin "P$2") (pinfunction "2_P$2") (pintype "bidirectional"))
      (node (ref "SW2") (pin "1") (pinfunction "A0_1") (pintype "bidirectional"))
      (node (ref "SW2") (pin "2") (pinfunction "A1_2") (pintype "bidirectional"))
    )
    (net (code "51") (name "SW") (class "Default")
      (node (ref "C21") (pin "P$1") (pinfunction "1_P$1") (pintype "bidirectional"))
      (node (ref "L1") (pin "1") (pinfunction "1_1") (pintype "bidirectional"))
      (node (ref "U3") (pin "2") (pinfunction "SW_2") (pintype "bidirectional"))
    )
    (net (code "52") (name "SW2") (class "Default")
      (node (ref "C27") (pin "P$1") (pinfunction "1_P$1") (pintype "bidirectional"))
      (node (ref "L2") (pin "1") (pinfunction "1_1") (pintype "bidirectional"))
      (node (ref "U4") (pin "2") (pinfunction "SW_2") (pintype "bidirectional"))
    )
    (net (code "53") (name "TCK_SWCLK") (class "Default")
      (node (ref "IC5") (pin "A14") (pinfunction "PA14_A14") (pintype "bidirectional"))
      (node (ref "JP2") (pin "4") (pinfunction "4_4") (pintype "passive"))
    )
    (net (code "54") (name "TDI") (class "Default")
      (node (ref "IC5") (pin "A13") (pinfunction "PA15_A13") (pintype "bidirectional"))
      (node (ref "JP2") (pin "8") (pinfunction "8_8") (pintype "passive"))
    )
    (net (code "55") (name "TDO") (class "Default")
      (node (ref "IC5") (pin "A10") (pinfunction "PB3_A10") (pintype "bidirectional"))
      (node (ref "JP2") (pin "6") (pinfunction "6_6") (pintype "passive"))
    )
    (net (code "56") (name "TFT_LED_K") (class "Default")
      (node (ref "J1") (pin "1") (pinfunction "1_1") (pintype "passive"))
      (node (ref "T1") (pin "3") (pinfunction "C_3") (pintype "passive"))
    )
    (net (code "57") (name "TFT_XL") (class "Default")
      (node (ref "J1") (pin "46") (pinfunction "46_46") (pintype "passive"))
    )
    (net (code "58") (name "TFT_XR") (class "Default")
      (node (ref "J1") (pin "44") (pinfunction "44_44") (pintype "passive"))
    )
    (net (code "59") (name "TFT_YD") (class "Default")
      (node (ref "J1") (pin "45") (pinfunction "45_45") (pintype "passive"))
    )
    (net (code "60") (name "TFT_YU") (class "Default")
      (node (ref "J1") (pin "47") (pinfunction "47_47") (pintype "passive"))
    )
    (net (code "61") (name "TMS_SWDIO") (class "Default")
      (node (ref "IC5") (pin "A15") (pinfunction "PA13_A15") (pintype "bidirectional"))
      (node (ref "JP2") (pin "2") (pinfunction "2_2") (pintype "passive"))
    )
    (net (code "62") (name "TRST") (class "Default")
      (node (ref "IC5") (pin "A9") (pinfunction "PB4_A9") (pintype "bidirectional"))
      (node (ref "JP2") (pin "7") (pinfunction "7_7") (pintype "passive"))
    )
    (net (code "63") (name "VBST") (class "Default")
      (node (ref "C21") (pin "P$2") (pinfunction "2_P$2") (pintype "bidirectional"))
      (node (ref "U3") (pin "6") (pinfunction "VBST_6") (pintype "bidirectional"))
    )
    (net (code "64") (name "VBST2") (class "Default")
      (node (ref "C27") (pin "P$2") (pinfunction "2_P$2") (pintype "bidirectional"))
      (node (ref "U4") (pin "6") (pinfunction "VBST_6") (pintype "bidirectional"))
    )
    (net (code "65") (name "VCAP1") (class "Default")
      (node (ref "C3") (pin "1") (pinfunction "1_1") (pintype "bidirectional"))
      (node (ref "IC5") (pin "L11") (pinfunction "VCAP1_L11") (pintype "power_in"))
    )
    (net (code "66") (name "VCAP2") (class "Default")
      (node (ref "C4") (pin "1") (pinfunction "1_1") (pintype "bidirectional"))
      (node (ref "IC5") (pin "E11") (pinfunction "VCAP2_E11") (pintype "power_in"))
    )
    (net (code "67") (name "VCC_BLED") (class "Default")
      (node (ref "J1") (pin "2") (pinfunction "2_2") (pintype "passive"))
      (node (ref "J1") (pin "3") (pinfunction "3_3") (pintype "passive"))
      (node (ref "J1") (pin "4") (pinfunction "4_4") (pintype "passive"))
      (node (ref "J1") (pin "5") (pinfunction "5_5") (pintype "passive"))
    )
    (net (code "68") (name "VDD") (class "Default")
      (node (ref "C10") (pin "P$1") (pinfunction "1_P$1") (pintype "bidirectional"))
      (node (ref "C24") (pin "P$1") (pinfunction "1_P$1") (pintype "bidirectional"))
      (node (ref "C25") (pin "P$1") (pinfunction "1_P$1") (pintype "bidirectional"))
      (node (ref "C26") (pin "P$1") (pinfunction "1_P$1") (pintype "bidirectional"))
      (node (ref "C32") (pin "2") (pinfunction "2_2") (pintype "passive"))
      (node (ref "C33") (pin "2") (pinfunction "2_2") (pintype "passive"))
      (node (ref "C34") (pin "2") (pinfunction "2_2") (pintype "passive"))
      (node (ref "C35") (pin "2") (pinfunction "2_2") (pintype "passive"))
      (node (ref "C36") (pin "2") (pinfunction "2_2") (pintype "passive"))
      (node (ref "C37") (pin "2") (pinfunction "2_2") (pintype "passive"))
      (node (ref "C38") (pin "2") (pinfunction "2_2") (pintype "passive"))
      (node (ref "C39") (pin "2") (pinfunction "2_2") (pintype "passive"))
      (node (ref "C40") (pin "2") (pinfunction "2_2") (pintype "passive"))
      (node (ref "C41") (pin "2") (pinfunction "2_2") (pintype "passive"))
      (node (ref "C42") (pin "2") (pinfunction "2_2") (pintype "passive"))
      (node (ref "C43") (pin "2") (pinfunction "2_2") (pintype "passive"))
      (node (ref "C44") (pin "2") (pinfunction "2_2") (pintype "passive"))
      (node (ref "C45") (pin "2") (pinfunction "2_2") (pintype "passive"))
      (node (ref "C46") (pin "2") (pinfunction "2_2") (pintype "passive"))
      (node (ref "C47") (pin "2") (pinfunction "2_2") (pintype "passive"))
      (node (ref "C48") (pin "2") (pinfunction "2_2") (pintype "passive"))
      (node (ref "C49") (pin "2") (pinfunction "2_2") (pintype "passive"))
      (node (ref "C50") (pin "2") (pinfunction "2_2") (pintype "passive"))
      (node (ref "FB1") (pin "P$1") (pinfunction "1_P$1") (pintype "bidirectional"))
      (node (ref "IC5") (pin "C1") (pinfunction "VBAT_C1") (pintype "power_in"))
      (node (ref "IC5") (pin "E10") (pinfunction "VDD_E10") (pintype "power_in"))
      (node (ref "IC5") (pin "E5") (pinfunction "PDR_ON_E5") (pintype "input"))
      (node (ref "IC5") (pin "E7") (pinfunction "VDD_E7") (pintype "power_in"))
      (node (ref "IC5") (pin "E8") (pinfunction "VDD_E8") (pintype "power_in"))
      (node (ref "IC5") (pin "E9") (pinfunction "VDD_E9") (pintype "power_in"))
      (node (ref "IC5") (pin "F11") (pinfunction "VDD_F11") (pintype "power_in"))
      (node (ref "IC5") (pin "F4") (pinfunction "VDD_F4") (pintype "power_in"))
      (node (ref "IC5") (pin "F5") (pinfunction "VDD_F5") (pintype "power_in"))
      (node (ref "IC5") (pin "G11") (pinfunction "VDD_G11") (pintype "power_in"))
      (node (ref "IC5") (pin "G5") (pinfunction "VDD_G5") (pintype "power_in"))
      (node (ref "IC5") (pin "H11") (pinfunction "VDD_H11") (pintype "power_in"))
      (node (ref "IC5") (pin "H5") (pinfunction "VDD_H5") (pintype "power_in"))
      (node (ref "IC5") (pin "J11") (pinfunction "VDD_J11") (pintype "power_in"))
      (node (ref "IC5") (pin "J5") (pinfunction "VDD_J5") (pintype "power_in"))
      (node (ref "IC5") (pin "K11") (pinfunction "VDD_K11") (pintype "power_in"))
      (node (ref "IC5") (pin "K5") (pinfunction "VDD_K5") (pintype "power_in"))
      (node (ref "IC5") (pin "L10") (pinfunction "VDD_L10") (pintype "power_in"))
      (node (ref "IC5") (pin "L7") (pinfunction "VDD_L7") (pintype "power_in"))
      (node (ref "IC5") (pin "L8") (pinfunction "VDD_L8") (pintype "power_in"))
      (node (ref "IC5") (pin "L9") (pinfunction "VDD_L9") (pintype "power_in"))
      (node (ref "J1") (pin "40") (pinfunction "40_40") (pintype "passive"))
      (node (ref "J1") (pin "41") (pinfunction "41_41") (pintype "passive"))
      (node (ref "J1") (pin "42") (pinfunction "42_42") (pintype "passive"))
      (node (ref "J1") (pin "9") (pinfunction "9_9") (pintype "passive"))
      (node (ref "JP2") (pin "1") (pinfunction "1_1") (pintype "passive"))
      (node (ref "L1") (pin "2") (pinfunction "2_2") (pintype "bidirectional"))
      (node (ref "R13") (pin "P$2") (pinfunction "2_P$2") (pintype "bidirectional"))
      (node (ref "R14") (pin "P$2") (pinfunction "2_P$2") (pintype "bidirectional"))
      (node (ref "R15") (pin "P$2") (pinfunction "2_P$2") (pintype "bidirectional"))
      (node (ref "R16") (pin "P$2") (pinfunction "2_P$2") (pintype "bidirectional"))
      (node (ref "R19") (pin "P$1") (pinfunction "1_P$1") (pintype "bidirectional"))
      (node (ref "R2") (pin "P$2") (pinfunction "2_P$2") (pintype "bidirectional"))
      (node (ref "R9") (pin "P$2") (pinfunction "2_P$2") (pintype "bidirectional"))
    )
    (net (code "69") (name "VDDA") (class "Default")
      (node (ref "C11") (pin "P$1") (pinfunction "1_P$1") (pintype "bidirectional"))
      (node (ref "C18") (pin "1") (pinfunction "1_1") (pintype "bidirectional"))
      (node (ref "C8") (pin "P$1") (pinfunction "1_P$1") (pintype "bidirectional"))
      (node (ref "C9") (pin "1") (pinfunction "1_1") (pintype "bidirectional"))
      (node (ref "FB1") (pin "P$2") (pinfunction "2_P$2") (pintype "bidirectional"))
      (node (ref "IC5") (pin "R1") (pinfunction "VDDA_R1") (pintype "power_in"))
    )
    (net (code "70") (name "VFB") (class "Default")
      (node (ref "R10") (pin "P$2") (pinfunction "2_P$2") (pintype "bidirectional"))
      (node (ref "R9") (pin "P$1") (pinfunction "1_P$1") (pintype "bidirectional"))
      (node (ref "U3") (pin "4") (pinfunction "VFB_4") (pintype "bidirectional"))
    )
    (net (code "71") (name "VFB2") (class "Default")
      (node (ref "R11") (pin "P$1") (pinfunction "1_P$1") (pintype "bidirectional"))
      (node (ref "R12") (pin "P$2") (pinfunction "2_P$2") (pintype "bidirectional"))
      (node (ref "U4") (pin "4") (pinfunction "VFB_4") (pintype "bidirectional"))
    )
    (net (code "72") (name "VIN_CHARGER") (class "Default")
      (node (ref "C1") (pin "1") (pinfunction "1_1") (pintype "bidirectional"))
      (node (ref "C16") (pin "1") (pinfunction "1_1") (pintype "bidirectional"))
      (node (ref "C30") (pin "P$1") (pinfunction "1_P$1") (pintype "bidirectional"))
      (node (ref "C31") (pin "P$1") (pinfunction "1_P$1") (pintype "bidirectional"))
      (node (ref "L2") (pin "2") (pinfunction "2_2") (pintype "bidirectional"))
      (node (ref "R11") (pin "P$2") (pinfunction "2_P$2") (pintype "bidirectional"))
      (node (ref "U1") (pin "4") (pinfunction "VIN_4") (pintype "bidirectional"))
      (node (ref "U2") (pin "4") (pinfunction "VIN_4") (pintype "bidirectional"))
    )
    (net (code "73") (name "VREF+") (class "Default")
      (node (ref "IC5") (pin "P1") (pinfunction "VREF+_P1") (pintype "power_in"))
    )
    (net (code "74") (name "unconnected-(IC1-+VS-Pad7)") (class "Default")
      (node (ref "IC1") (pin "7") (pinfunction "+VS_7") (pintype "input"))
    )
    (net (code "75") (name "unconnected-(IC1-OFF-Pad1)") (class "Default")
      (node (ref "IC1") (pin "1") (pinfunction "OFF_1") (pintype "passive"))
    )
    (net (code "76") (name "unconnected-(IC1-OFF-Pad5)") (class "Default")
      (node (ref "IC1") (pin "5") (pinfunction "OFF_5") (pintype "passive"))
    )
    (net (code "77") (name "unconnected-(IC3-+VS-Pad7)") (class "Default")
      (node (ref "IC3") (pin "7") (pinfunction "+VS_7") (pintype "input"))
    )
    (net (code "78") (name "unconnected-(IC3-OFF-Pad1)") (class "Default")
      (node (ref "IC3") (pin "1") (pinfunction "OFF_1") (pintype "passive"))
    )
    (net (code "79") (name "unconnected-(IC3-OFF-Pad5)") (class "Default")
      (node (ref "IC3") (pin "5") (pinfunction "OFF_5") (pintype "passive"))
    )
    (net (code "80") (name "unconnected-(IC5A-PA0-PadN3)") (class "Default")
      (node (ref "IC5") (pin "N3") (pinfunction "PA0_N3") (pintype "bidirectional"))
    )
    (net (code "81") (name "unconnected-(IC5A-PA3-PadR2)") (class "Default")
      (node (ref "IC5") (pin "R2") (pinfunction "PA3_R2") (pintype "bidirectional"))
    )
    (net (code "82") (name "unconnected-(IC5A-PA4-PadN4)") (class "Default")
      (node (ref "IC5") (pin "N4") (pinfunction "PA4_N4") (pintype "bidirectional"))
    )
    (net (code "83") (name "unconnected-(IC5A-PA5-PadP4)") (class "Default")
      (node (ref "IC5") (pin "P4") (pinfunction "PA5_P4") (pintype "bidirectional"))
    )
    (net (code "84") (name "unconnected-(IC5A-PA6-PadP3)") (class "Default")
      (node (ref "IC5") (pin "P3") (pinfunction "PA6_P3") (pintype "bidirectional"))
    )
    (net (code "85") (name "unconnected-(IC5A-PA7-PadR3)") (class "Default")
      (node (ref "IC5") (pin "R3") (pinfunction "PA7_R3") (pintype "bidirectional"))
    )
    (net (code "86") (name "unconnected-(IC5A-PA8-PadF15)") (class "Default")
      (node (ref "IC5") (pin "F15") (pinfunction "PA8_F15") (pintype "bidirectional"))
    )
    (net (code "87") (name "unconnected-(IC5A-PA9-PadE15)") (class "Default")
      (node (ref "IC5") (pin "E15") (pinfunction "PA9_E15") (pintype "bidirectional"))
    )
    (net (code "88") (name "unconnected-(IC5A-PA10-PadD15)") (class "Default")
      (node (ref "IC5") (pin "D15") (pinfunction "PA10_D15") (pintype "bidirectional"))
    )
    (net (code "89") (name "unconnected-(IC5A-PA11-PadC15)") (class "Default")
      (node (ref "IC5") (pin "C15") (pinfunction "PA11_C15") (pintype "bidirectional"))
    )
    (net (code "90") (name "unconnected-(IC5A-PA12-PadB15)") (class "Default")
      (node (ref "IC5") (pin "B15") (pinfunction "PA12_B15") (pintype "bidirectional"))
    )
    (net (code "91") (name "unconnected-(IC5A-PB0-PadR5)") (class "Default")
      (node (ref "IC5") (pin "R5") (pinfunction "PB0_R5") (pintype "bidirectional"))
    )
    (net (code "92") (name "unconnected-(IC5A-PB1-PadR4)") (class "Default")
      (node (ref "IC5") (pin "R4") (pinfunction "PB1_R4") (pintype "bidirectional"))
    )
    (net (code "93") (name "unconnected-(IC5A-PB2-PadM5)") (class "Default")
      (node (ref "IC5") (pin "M5") (pinfunction "PB2_M5") (pintype "bidirectional"))
    )
    (net (code "94") (name "unconnected-(IC5A-PB5-PadA8)") (class "Default")
      (node (ref "IC5") (pin "A8") (pinfunction "PB5_A8") (pintype "bidirectional"))
    )
    (net (code "95") (name "unconnected-(IC5A-PB6-PadB6)") (class "Default")
      (node (ref "IC5") (pin "B6") (pinfunction "PB6_B6") (pintype "bidirectional"))
    )
    (net (code "96") (name "unconnected-(IC5A-PB7-PadB5)") (class "Default")
      (node (ref "IC5") (pin "B5") (pinfunction "PB7_B5") (pintype "bidirectional"))
    )
    (net (code "97") (name "unconnected-(IC5A-PB8-PadA7)") (class "Default")
      (node (ref "IC5") (pin "A7") (pinfunction "PB8_A7") (pintype "bidirectional"))
    )
    (net (code "98") (name "unconnected-(IC5A-PB9-PadB4)") (class "Default")
      (node (ref "IC5") (pin "B4") (pinfunction "PB9_B4") (pintype "bidirectional"))
    )
    (net (code "99") (name "unconnected-(IC5A-PB10-PadP12)") (class "Default")
      (node (ref "IC5") (pin "P12") (pinfunction "PB10_P12") (pintype "bidirectional"))
    )
    (net (code "100") (name "unconnected-(IC5A-PB11-PadR13)") (class "Default")
      (node (ref "IC5") (pin "R13") (pinfunction "PB11_R13") (pintype "bidirectional"))
    )
    (net (code "101") (name "unconnected-(IC5A-PB12-PadL13)") (class "Default")
      (node (ref "IC5") (pin "L13") (pinfunction "PB12_L13") (pintype "bidirectional"))
    )
    (net (code "102") (name "unconnected-(IC5A-PC0-PadM2)") (class "Default")
      (node (ref "IC5") (pin "M2") (pinfunction "PC0_M2") (pintype "bidirectional"))
    )
    (net (code "103") (name "unconnected-(IC5A-PC1-PadM3)") (class "Default")
      (node (ref "IC5") (pin "M3") (pinfunction "PC1_M3") (pintype "bidirectional"))
    )
    (net (code "104") (name "unconnected-(IC5A-PC2-PadM4)") (class "Default")
      (node (ref "IC5") (pin "M4") (pinfunction "PC2_M4") (pintype "bidirectional"))
    )
    (net (code "105") (name "unconnected-(IC5A-PC3-PadL4)") (class "Default")
      (node (ref "IC5") (pin "L4") (pinfunction "PC3_L4") (pintype "bidirectional"))
    )
    (net (code "106") (name "unconnected-(IC5A-PC4-PadN5)") (class "Default")
      (node (ref "IC5") (pin "N5") (pinfunction "PC4_N5") (pintype "bidirectional"))
    )
    (net (code "107") (name "unconnected-(IC5A-PC5-PadP5)") (class "Default")
      (node (ref "IC5") (pin "P5") (pinfunction "PC5_P5") (pintype "bidirectional"))
    )
    (net (code "108") (name "unconnected-(IC5A-PC6-PadH15)") (class "Default")
      (node (ref "IC5") (pin "H15") (pinfunction "PC6_H15") (pintype "bidirectional"))
    )
    (net (code "109") (name "unconnected-(IC5A-PC7-PadG15)") (class "Default")
      (node (ref "IC5") (pin "G15") (pinfunction "PC7_G15") (pintype "bidirectional"))
    )
    (net (code "110") (name "unconnected-(IC5A-PC8-PadG14)") (class "Default")
      (node (ref "IC5") (pin "G14") (pinfunction "PC8_G14") (pintype "bidirectional"))
    )
    (net (code "111") (name "unconnected-(IC5A-PC9-PadF14)") (class "Default")
      (node (ref "IC5") (pin "F14") (pinfunction "PC9_F14") (pintype "bidirectional"))
    )
    (net (code "112") (name "unconnected-(IC5A-PC10-PadB14)") (class "Default")
      (node (ref "IC5") (pin "B14") (pinfunction "PC10_B14") (pintype "bidirectional"))
    )
    (net (code "113") (name "unconnected-(IC5A-PC11-PadB13)") (class "Default")
      (node (ref "IC5") (pin "B13") (pinfunction "PC11_B13") (pintype "bidirectional"))
    )
    (net (code "114") (name "unconnected-(IC5A-PC12-PadA12)") (class "Default")
      (node (ref "IC5") (pin "A12") (pinfunction "PC12_A12") (pintype "bidirectional"))
    )
    (net (code "115") (name "unconnected-(IC5A-PC13-PadD1)") (class "Default")
      (node (ref "IC5") (pin "D1") (pinfunction "PC13_D1") (pintype "bidirectional"))
    )
    (net (code "116") (name "unconnected-(IC5A-PC14-PadE1)") (class "Default")
      (node (ref "IC5") (pin "E1") (pinfunction "PC14_E1") (pintype "bidirectional"))
    )
    (net (code "117") (name "unconnected-(IC5A-PC15-PadF1)") (class "Default")
      (node (ref "IC5") (pin "F1") (pinfunction "PC15_F1") (pintype "bidirectional"))
    )
    (net (code "118") (name "unconnected-(IC5A-PD2-PadD12)") (class "Default")
      (node (ref "IC5") (pin "D12") (pinfunction "PD2_D12") (pintype "bidirectional"))
    )
    (net (code "119") (name "unconnected-(IC5A-PD3-PadC11)") (class "Default")
      (node (ref "IC5") (pin "C11") (pinfunction "PD3_C11") (pintype "bidirectional"))
    )
    (net (code "120") (name "unconnected-(IC5A-PD6-PadB11)") (class "Default")
      (node (ref "IC5") (pin "B11") (pinfunction "PD6_B11") (pintype "bidirectional"))
    )
    (net (code "121") (name "unconnected-(IC5A-PD11-PadN10)") (class "Default")
      (node (ref "IC5") (pin "N10") (pinfunction "PD11_N10") (pintype "bidirectional"))
    )
    (net (code "122") (name "unconnected-(IC5A-PD12-PadM10)") (class "Default")
      (node (ref "IC5") (pin "M10") (pinfunction "PD12_M10") (pintype "bidirectional"))
    )
    (net (code "123") (name "unconnected-(IC5A-PD13-PadM11)") (class "Default")
      (node (ref "IC5") (pin "M11") (pinfunction "PD13_M11") (pintype "bidirectional"))
    )
    (net (code "124") (name "unconnected-(IC5A-PE0-PadA6)") (class "Default")
      (node (ref "IC5") (pin "A6") (pinfunction "PE0_A6") (pintype "bidirectional"))
    )
    (net (code "125") (name "unconnected-(IC5A-PE1-PadA5)") (class "Default")
      (node (ref "IC5") (pin "A5") (pinfunction "PE1_A5") (pintype "bidirectional"))
    )
    (net (code "126") (name "unconnected-(IC5A-PE2-PadA3)") (class "Default")
      (node (ref "IC5") (pin "A3") (pinfunction "PE2_A3") (pintype "bidirectional"))
    )
    (net (code "127") (name "unconnected-(IC5A-PE3-PadA2)") (class "Default")
      (node (ref "IC5") (pin "A2") (pinfunction "PE3_A2") (pintype "bidirectional"))
    )
    (net (code "128") (name "unconnected-(IC5A-PE4-PadA1)") (class "Default")
      (node (ref "IC5") (pin "A1") (pinfunction "PE4_A1") (pintype "bidirectional"))
    )
    (net (code "129") (name "unconnected-(IC5A-PE5-PadB1)") (class "Default")
      (node (ref "IC5") (pin "B1") (pinfunction "PE5_B1") (pintype "bidirectional"))
    )
    (net (code "130") (name "unconnected-(IC5A-PE6-PadB2)") (class "Default")
      (node (ref "IC5") (pin "B2") (pinfunction "PE6_B2") (pintype "bidirectional"))
    )
    (net (code "131") (name "unconnected-(IC5A-PF1-PadE2)") (class "Default")
      (node (ref "IC5") (pin "E2") (pinfunction "PF1_E2") (pintype "bidirectional"))
    )
    (net (code "132") (name "unconnected-(IC5A-PF2-PadG2)") (class "Default")
      (node (ref "IC5") (pin "G2") (pinfunction "PF2_G2") (pintype "bidirectional"))
    )
    (net (code "133") (name "unconnected-(IC5A-PF3-PadH2)") (class "Default")
      (node (ref "IC5") (pin "H2") (pinfunction "PF3_H2") (pintype "bidirectional"))
    )
    (net (code "134") (name "unconnected-(IC5A-PF4-PadJ2)") (class "Default")
      (node (ref "IC5") (pin "J2") (pinfunction "PF4_J2") (pintype "bidirectional"))
    )
    (net (code "135") (name "unconnected-(IC5A-PF5-PadK3)") (class "Default")
      (node (ref "IC5") (pin "K3") (pinfunction "PF5_K3") (pintype "bidirectional"))
    )
    (net (code "136") (name "unconnected-(IC5A-PF6-PadK2)") (class "Default")
      (node (ref "IC5") (pin "K2") (pinfunction "PF6_K2") (pintype "bidirectional"))
    )
    (net (code "137") (name "unconnected-(IC5A-PF7-PadK1)") (class "Default")
      (node (ref "IC5") (pin "K1") (pinfunction "PF7_K1") (pintype "bidirectional"))
    )
    (net (code "138") (name "unconnected-(IC5A-PF8-PadL3)") (class "Default")
      (node (ref "IC5") (pin "L3") (pinfunction "PF8_L3") (pintype "bidirectional"))
    )
    (net (code "139") (name "unconnected-(IC5A-PF9-PadL2)") (class "Default")
      (node (ref "IC5") (pin "L2") (pinfunction "PF9_L2") (pintype "bidirectional"))
    )
    (net (code "140") (name "unconnected-(IC5A-PF10-PadL1)") (class "Default")
      (node (ref "IC5") (pin "L1") (pinfunction "PF10_L1") (pintype "bidirectional"))
    )
    (net (code "141") (name "unconnected-(IC5A-PF11-PadP8)") (class "Default")
      (node (ref "IC5") (pin "P8") (pinfunction "PF11_P8") (pintype "bidirectional"))
    )
    (net (code "142") (name "unconnected-(IC5A-PF12-PadM6)") (class "Default")
      (node (ref "IC5") (pin "M6") (pinfunction "PF12_M6") (pintype "bidirectional"))
    )
    (net (code "143") (name "unconnected-(IC5A-PF13-PadN6)") (class "Default")
      (node (ref "IC5") (pin "N6") (pinfunction "PF13_N6") (pintype "bidirectional"))
    )
    (net (code "144") (name "unconnected-(IC5A-PF14-PadP6)") (class "Default")
      (node (ref "IC5") (pin "P6") (pinfunction "PF14_P6") (pintype "bidirectional"))
    )
    (net (code "145") (name "unconnected-(IC5A-PF15-PadM8)") (class "Default")
      (node (ref "IC5") (pin "M8") (pinfunction "PF15_M8") (pintype "bidirectional"))
    )
    (net (code "146") (name "unconnected-(IC5A-PG0-PadN7)") (class "Default")
      (node (ref "IC5") (pin "N7") (pinfunction "PG0_N7") (pintype "bidirectional"))
    )
    (net (code "147") (name "unconnected-(IC5A-PG1-PadM7)") (class "Default")
      (node (ref "IC5") (pin "M7") (pinfunction "PG1_M7") (pintype "bidirectional"))
    )
    (net (code "148") (name "unconnected-(IC5A-PG2-PadM13)") (class "Default")
      (node (ref "IC5") (pin "M13") (pinfunction "PG2_M13") (pintype "bidirectional"))
    )
    (net (code "149") (name "unconnected-(IC5A-PG3-PadM12)") (class "Default")
      (node (ref "IC5") (pin "M12") (pinfunction "PG3_M12") (pintype "bidirectional"))
    )
    (net (code "150") (name "unconnected-(IC5A-PG4-PadN12)") (class "Default")
      (node (ref "IC5") (pin "N12") (pinfunction "PG4_N12") (pintype "bidirectional"))
    )
    (net (code "151") (name "unconnected-(IC5A-PG5-PadN11)") (class "Default")
      (node (ref "IC5") (pin "N11") (pinfunction "PG5_N11") (pintype "bidirectional"))
    )
    (net (code "152") (name "unconnected-(IC5A-PG6-PadJ15)") (class "Default")
      (node (ref "IC5") (pin "J15") (pinfunction "PG6_J15") (pintype "bidirectional"))
    )
    (net (code "153") (name "unconnected-(IC5A-PG7-PadJ14)") (class "Default")
      (node (ref "IC5") (pin "J14") (pinfunction "PG7_J14") (pintype "bidirectional"))
    )
    (net (code "154") (name "unconnected-(IC5A-PG8-PadH14)") (class "Default")
      (node (ref "IC5") (pin "H14") (pinfunction "PG8_H14") (pintype "bidirectional"))
    )
    (net (code "155") (name "unconnected-(IC5A-PG9-PadD9)") (class "Default")
      (node (ref "IC5") (pin "D9") (pinfunction "PG9_D9") (pintype "bidirectional"))
    )
    (net (code "156") (name "unconnected-(IC5A-PG10-PadC8)") (class "Default")
      (node (ref "IC5") (pin "C8") (pinfunction "PG10_C8") (pintype "bidirectional"))
    )
    (net (code "157") (name "unconnected-(IC5A-PG11-PadB8)") (class "Default")
      (node (ref "IC5") (pin "B8") (pinfunction "PG11_B8") (pintype "bidirectional"))
    )
    (net (code "158") (name "unconnected-(IC5A-PG12-PadC7)") (class "Default")
      (node (ref "IC5") (pin "C7") (pinfunction "PG12_C7") (pintype "bidirectional"))
    )
    (net (code "159") (name "unconnected-(IC5A-PG13-PadB3)") (class "Default")
      (node (ref "IC5") (pin "B3") (pinfunction "PG13_B3") (pintype "bidirectional"))
    )
    (net (code "160") (name "unconnected-(IC5A-PG14-PadA4)") (class "Default")
      (node (ref "IC5") (pin "A4") (pinfunction "PG14_A4") (pintype "bidirectional"))
    )
    (net (code "161") (name "unconnected-(IC5A-PG15-PadB7)") (class "Default")
      (node (ref "IC5") (pin "B7") (pinfunction "PG15_B7") (pintype "bidirectional"))
    )
    (net (code "162") (name "unconnected-(IC5A-PH2-PadK4)") (class "Default")
      (node (ref "IC5") (pin "K4") (pinfunction "PH2_K4") (pintype "bidirectional"))
    )
    (net (code "163") (name "unconnected-(IC5A-PH3-PadJ4)") (class "Default")
      (node (ref "IC5") (pin "J4") (pinfunction "PH3_J4") (pintype "bidirectional"))
    )
    (net (code "164") (name "unconnected-(IC5A-PH4-PadH4)") (class "Default")
      (node (ref "IC5") (pin "H4") (pinfunction "PH4_H4") (pintype "bidirectional"))
    )
    (net (code "165") (name "unconnected-(IC5A-PH5-PadJ3)") (class "Default")
      (node (ref "IC5") (pin "J3") (pinfunction "PH5_J3") (pintype "bidirectional"))
    )
    (net (code "166") (name "unconnected-(IC5A-PH6-PadP13)") (class "Default")
      (node (ref "IC5") (pin "P13") (pinfunction "PH6_P13") (pintype "bidirectional"))
    )
    (net (code "167") (name "unconnected-(IC5A-PH7-PadN13)") (class "Default")
      (node (ref "IC5") (pin "N13") (pinfunction "PH7_N13") (pintype "bidirectional"))
    )
    (net (code "168") (name "unconnected-(IC5A-PH13-PadE12)") (class "Default")
      (node (ref "IC5") (pin "E12") (pinfunction "PH13_E12") (pintype "bidirectional"))
    )
    (net (code "169") (name "unconnected-(IC5A-PH14-PadE13)") (class "Default")
      (node (ref "IC5") (pin "E13") (pinfunction "PH14_E13") (pintype "bidirectional"))
    )
    (net (code "170") (name "unconnected-(IC5A-PH15-PadD13)") (class "Default")
      (node (ref "IC5") (pin "D13") (pinfunction "PH15_D13") (pintype "bidirectional"))
    )
    (net (code "171") (name "unconnected-(IC5A-PI0-PadE14)") (class "Default")
      (node (ref "IC5") (pin "E14") (pinfunction "PI0_E14") (pintype "bidirectional"))
    )
    (net (code "172") (name "unconnected-(IC5A-PI1-PadD14)") (class "Default")
      (node (ref "IC5") (pin "D14") (pinfunction "PI1_D14") (pintype "bidirectional"))
    )
    (net (code "173") (name "unconnected-(IC5A-PI2-PadC14)") (class "Default")
      (node (ref "IC5") (pin "C14") (pinfunction "PI2_C14") (pintype "bidirectional"))
    )
    (net (code "174") (name "unconnected-(IC5A-PI3-PadC13)") (class "Default")
      (node (ref "IC5") (pin "C13") (pinfunction "PI3_C13") (pintype "bidirectional"))
    )
    (net (code "175") (name "unconnected-(IC5A-PI4-PadC3)") (class "Default")
      (node (ref "IC5") (pin "C3") (pinfunction "PI4_C3") (pintype "bidirectional"))
    )
    (net (code "176") (name "unconnected-(IC5A-PI5-PadD3)") (class "Default")
      (node (ref "IC5") (pin "D3") (pinfunction "PI5_D3") (pintype "bidirectional"))
    )
    (net (code "177") (name "unconnected-(IC5A-PI6-PadD6)") (class "Default")
      (node (ref "IC5") (pin "D6") (pinfunction "PI6_D6") (pintype "bidirectional"))
    )
    (net (code "178") (name "unconnected-(IC5A-PI7-PadD4)") (class "Default")
      (node (ref "IC5") (pin "D4") (pinfunction "PI7_D4") (pintype "bidirectional"))
    )
    (net (code "179") (name "unconnected-(IC5A-PI8-PadC2)") (class "Default")
      (node (ref "IC5") (pin "C2") (pinfunction "PI8_C2") (pintype "bidirectional"))
    )
    (net (code "180") (name "unconnected-(IC5A-PI9-PadE4)") (class "Default")
      (node (ref "IC5") (pin "E4") (pinfunction "PI9_E4") (pintype "bidirectional"))
    )
    (net (code "181") (name "unconnected-(IC5A-PI10-PadD5)") (class "Default")
      (node (ref "IC5") (pin "D5") (pinfunction "PI10_D5") (pintype "bidirectional"))
    )
    (net (code "182") (name "unconnected-(IC5A-PI11-PadF3)") (class "Default")
      (node (ref "IC5") (pin "F3") (pinfunction "PI11_F3") (pintype "bidirectional"))
    )
    (net (code "183") (name "unconnected-(IC5A-PI12-PadE3)") (class "Default")
      (node (ref "IC5") (pin "E3") (pinfunction "PI12_E3") (pintype "bidirectional"))
    )
    (net (code "184") (name "unconnected-(IC5A-PI13-PadG3)") (class "Default")
      (node (ref "IC5") (pin "G3") (pinfunction "PI13_G3") (pintype "bidirectional"))
    )
    (net (code "185") (name "unconnected-(IC5A-PI14-PadH3)") (class "Default")
      (node (ref "IC5") (pin "H3") (pinfunction "PI14_H3") (pintype "bidirectional"))
    )
    (net (code "186") (name "unconnected-(IC5A-PI15-PadG4)") (class "Default")
      (node (ref "IC5") (pin "G4") (pinfunction "PI15_G4") (pintype "bidirectional"))
    )
    (net (code "187") (name "unconnected-(IC5A-PJ0-PadR6)") (class "Default")
      (node (ref "IC5") (pin "R6") (pinfunction "PJ0_R6") (pintype "bidirectional"))
    )
    (net (code "188") (name "unconnected-(IC5A-PJ1-PadR7)") (class "Default")
      (node (ref "IC5") (pin "R7") (pinfunction "PJ1_R7") (pintype "bidirectional"))
    )
    (net (code "189") (name "unconnected-(IC5A-PJ2-PadP7)") (class "Default")
      (node (ref "IC5") (pin "P7") (pinfunction "PJ2_P7") (pintype "bidirectional"))
    )
    (net (code "190") (name "unconnected-(IC5A-PJ3-PadN8)") (class "Default")
      (node (ref "IC5") (pin "N8") (pinfunction "PJ3_N8") (pintype "bidirectional"))
    )
    (net (code "191") (name "unconnected-(IC5A-PJ4-PadM9)") (class "Default")
      (node (ref "IC5") (pin "M9") (pinfunction "PJ4_M9") (pintype "bidirectional"))
    )
    (net (code "192") (name "unconnected-(IC5A-PJ6-PadK12)") (class "Default")
      (node (ref "IC5") (pin "K12") (pinfunction "PJ6_K12") (pintype "bidirectional"))
    )
    (net (code "193") (name "unconnected-(IC5A-PJ7-PadJ12)") (class "Default")
      (node (ref "IC5") (pin "J12") (pinfunction "PJ7_J12") (pintype "bidirectional"))
    )
    (net (code "194") (name "unconnected-(IC5A-PJ8-PadH12)") (class "Default")
      (node (ref "IC5") (pin "H12") (pinfunction "PJ8_H12") (pintype "bidirectional"))
    )
    (net (code "195") (name "unconnected-(IC5A-PJ9-PadJ13)") (class "Default")
      (node (ref "IC5") (pin "J13") (pinfunction "PJ9_J13") (pintype "bidirectional"))
    )
    (net (code "196") (name "unconnected-(IC5A-PJ10-PadH13)") (class "Default")
      (node (ref "IC5") (pin "H13") (pinfunction "PJ10_H13") (pintype "bidirectional"))
    )
    (net (code "197") (name "unconnected-(IC5A-PJ11-PadG12)") (class "Default")
      (node (ref "IC5") (pin "G12") (pinfunction "PJ11_G12") (pintype "bidirectional"))
    )
    (net (code "198") (name "unconnected-(IC5A-PJ12-PadB10)") (class "Default")
      (node (ref "IC5") (pin "B10") (pinfunction "PJ12_B10") (pintype "bidirectional"))
    )
    (net (code "199") (name "unconnected-(IC5A-PJ13-PadB9)") (class "Default")
      (node (ref "IC5") (pin "B9") (pinfunction "PJ13_B9") (pintype "bidirectional"))
    )
    (net (code "200") (name "unconnected-(IC5A-PJ14-PadC9)") (class "Default")
      (node (ref "IC5") (pin "C9") (pinfunction "PJ14_C9") (pintype "bidirectional"))
    )
    (net (code "201") (name "unconnected-(IC5A-PJ15-PadD10)") (class "Default")
      (node (ref "IC5") (pin "D10") (pinfunction "PJ15_D10") (pintype "bidirectional"))
    )
    (net (code "202") (name "unconnected-(IC5A-PK0-PadG13)") (class "Default")
      (node (ref "IC5") (pin "G13") (pinfunction "PK0_G13") (pintype "bidirectional"))
    )
    (net (code "203") (name "unconnected-(IC5A-PK1-PadF12)") (class "Default")
      (node (ref "IC5") (pin "F12") (pinfunction "PK1_F12") (pintype "bidirectional"))
    )
    (net (code "204") (name "unconnected-(IC5A-PK2-PadF13)") (class "Default")
      (node (ref "IC5") (pin "F13") (pinfunction "PK2_F13") (pintype "bidirectional"))
    )
    (net (code "205") (name "unconnected-(IC5A-PK3-PadD8)") (class "Default")
      (node (ref "IC5") (pin "D8") (pinfunction "PK3_D8") (pintype "bidirectional"))
    )
    (net (code "206") (name "unconnected-(IC5A-PK4-PadD7)") (class "Default")
      (node (ref "IC5") (pin "D7") (pinfunction "PK4_D7") (pintype "bidirectional"))
    )
    (net (code "207") (name "unconnected-(IC5A-PK5-PadC6)") (class "Default")
      (node (ref "IC5") (pin "C6") (pinfunction "PK5_C6") (pintype "bidirectional"))
    )
    (net (code "208") (name "unconnected-(IC5A-PK6-PadC5)") (class "Default")
      (node (ref "IC5") (pin "C5") (pinfunction "PK6_C5") (pintype "bidirectional"))
    )
    (net (code "209") (name "unconnected-(IC5A-PK7-PadC4)") (class "Default")
      (node (ref "IC5") (pin "C4") (pinfunction "PK7_C4") (pintype "bidirectional"))
    )
    (net (code "210") (name "unconnected-(J1-Pad33)") (class "Default")
      (node (ref "J1") (pin "33") (pinfunction "33_33") (pintype "passive"))
    )
    (net (code "211") (name "unconnected-(J1-Pad39)") (class "Default")
      (node (ref "J1") (pin "39") (pinfunction "39_39") (pintype "passive"))
    )
    (net (code "212") (name "unconnected-(U$1-#RESET-Pad2)") (class "Default")
      (node (ref "U$1") (pin "2") (pinfunction "#RESET_2") (pintype "bidirectional"))
    )
    (net (code "213") (name "unconnected-(U$1-#SYNC-Pad16)") (class "Default")
      (node (ref "U$1") (pin "16") (pinfunction "#SYNC_16") (pintype "bidirectional"))
    )
    (net (code "214") (name "unconnected-(U$1-B1-Pad6)") (class "Default")
      (node (ref "U$1") (pin "6") (pinfunction "B1_6") (pintype "bidirectional"))
    )
    (net (code "215") (name "unconnected-(U$1-B2-Pad10)") (class "Default")
      (node (ref "U$1") (pin "10") (pinfunction "B2_10") (pintype "bidirectional"))
    )
    (net (code "216") (name "unconnected-(U$1-INDEP-Pad1)") (class "Default")
      (node (ref "U$1") (pin "1") (pinfunction "INDEP_1") (pintype "bidirectional"))
    )
    (net (code "217") (name "unconnected-(U$1-VDD-Pad11)") (class "Default")
      (node (ref "U$1") (pin "11") (pinfunction "VDD_11") (pintype "bidirectional"))
    )
    (net (code "218") (name "unconnected-(U$1-VLOGIC-Pad12)") (class "Default")
      (node (ref "U$1") (pin "12") (pinfunction "VLOGIC_12") (pintype "bidirectional"))
    )
    (net (code "219") (name "unconnected-(U1-TEMP-Pad1)") (class "Default")
      (node (ref "U1") (pin "1") (pinfunction "TEMP_1") (pintype "bidirectional"))
    )
    (net (code "220") (name "unconnected-(U2-TEMP-Pad1)") (class "Default")
      (node (ref "U2") (pin "1") (pinfunction "TEMP_1") (pintype "bidirectional"))
    )
  )
)
